# D_Output.net
KiCad netlist of a schematic drawn in Altium Designer
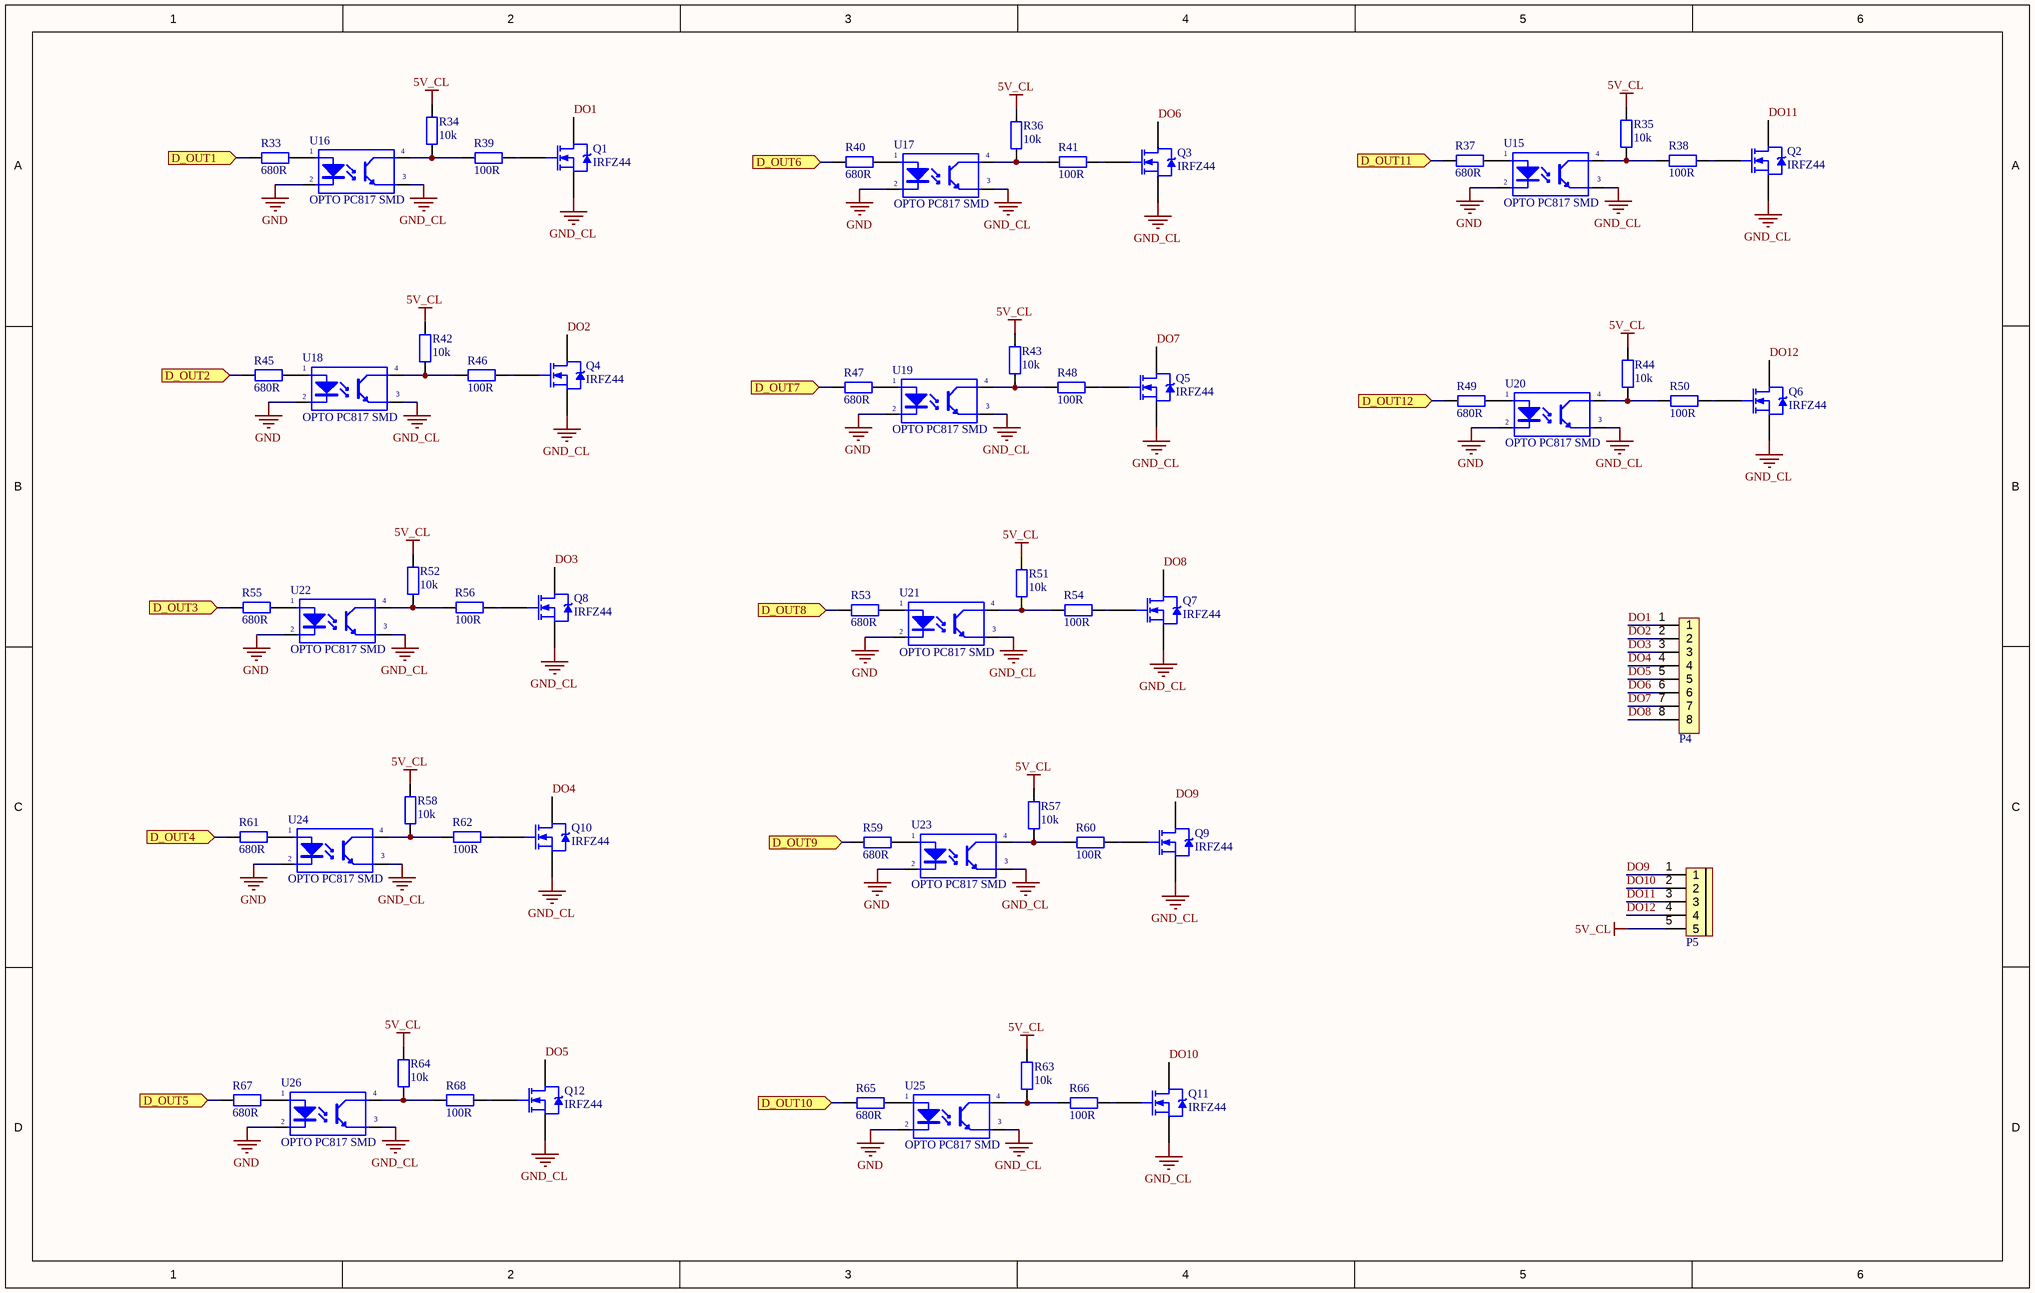
[diagram p0: D_Output.SchDoc]

(export (version "E")
  (design (tool "Eeschema 10.0.6"))
  (components
    (comp (ref "P4")
      (value "CON 8 EDG5.08")
      (footprint "CON 8 8EDG5.08")
      (description "Cắm")
      (libsource (lib "Altium_Lib_by_KhueNguyenCreator") (part "CON 8 EDG5.08"))
    )
    (comp (ref "P5")
      (value "CON 5 EDG5.08")
      (footprint "CON 5 5EDG5.08")
      (description "Cắm")
      (libsource (lib "Altium_Lib_by_KhueNguyenCreator") (part "CON 5 EDG5.08"))
    )
    (comp (ref "Q1")
      (value "IRFZ44")
      (footprint "TO220")
      (description "N-Channel Power MOSFET")
      (libsource (lib "Altium_Lib_by_KhueNguyenCreator") (part "IRFZ44 DIP"))
    )
    (comp (ref "Q2")
      (value "IRFZ44")
      (footprint "TO220")
      (description "N-Channel Power MOSFET")
      (libsource (lib "Altium_Lib_by_KhueNguyenCreator") (part "IRFZ44 DIP"))
    )
    (comp (ref "Q3")
      (value "IRFZ44")
      (footprint "TO220")
      (description "N-Channel Power MOSFET")
      (libsource (lib "Altium_Lib_by_KhueNguyenCreator") (part "IRFZ44 DIP"))
    )
    (comp (ref "Q4")
      (value "IRFZ44")
      (footprint "TO220")
      (description "N-Channel Power MOSFET")
      (libsource (lib "Altium_Lib_by_KhueNguyenCreator") (part "IRFZ44 DIP"))
    )
    (comp (ref "Q5")
      (value "IRFZ44")
      (footprint "TO220")
      (description "N-Channel Power MOSFET")
      (libsource (lib "Altium_Lib_by_KhueNguyenCreator") (part "IRFZ44 DIP"))
    )
    (comp (ref "Q6")
      (value "IRFZ44")
      (footprint "TO220")
      (description "N-Channel Power MOSFET")
      (libsource (lib "Altium_Lib_by_KhueNguyenCreator") (part "IRFZ44 DIP"))
    )
    (comp (ref "Q7")
      (value "IRFZ44")
      (footprint "TO220")
      (description "N-Channel Power MOSFET")
      (libsource (lib "Altium_Lib_by_KhueNguyenCreator") (part "IRFZ44 DIP"))
    )
    (comp (ref "Q8")
      (value "IRFZ44")
      (footprint "TO220")
      (description "N-Channel Power MOSFET")
      (libsource (lib "Altium_Lib_by_KhueNguyenCreator") (part "IRFZ44 DIP"))
    )
    (comp (ref "Q9")
      (value "IRFZ44")
      (footprint "TO220")
      (description "N-Channel Power MOSFET")
      (libsource (lib "Altium_Lib_by_KhueNguyenCreator") (part "IRFZ44 DIP"))
    )
    (comp (ref "Q10")
      (value "IRFZ44")
      (footprint "TO220")
      (description "N-Channel Power MOSFET")
      (libsource (lib "Altium_Lib_by_KhueNguyenCreator") (part "IRFZ44 DIP"))
    )
    (comp (ref "Q11")
      (value "IRFZ44")
      (footprint "TO220")
      (description "N-Channel Power MOSFET")
      (libsource (lib "Altium_Lib_by_KhueNguyenCreator") (part "IRFZ44 DIP"))
    )
    (comp (ref "Q12")
      (value "IRFZ44")
      (footprint "TO220")
      (description "N-Channel Power MOSFET")
      (libsource (lib "Altium_Lib_by_KhueNguyenCreator") (part "IRFZ44 DIP"))
    )
    (comp (ref "R33")
      (value "680R")
      (footprint "tro smd 0805")
      (description "Dán")
      (libsource (lib "Altium_Lib_by_KhueNguyenCreator") (part "Tro 0805 1% 680R"))
    )
    (comp (ref "R34")
      (value "10k")
      (footprint "tro smd 0805")
      (description "Dán")
      (libsource (lib "Altium_Lib_by_KhueNguyenCreator") (part "Tro 0805 1% 10k"))
    )
    (comp (ref "R35")
      (value "10k")
      (footprint "tro smd 0805")
      (description "Dán")
      (libsource (lib "Altium_Lib_by_KhueNguyenCreator") (part "Tro 0805 1% 10k"))
    )
    (comp (ref "R36")
      (value "10k")
      (footprint "tro smd 0805")
      (description "Dán")
      (libsource (lib "Altium_Lib_by_KhueNguyenCreator") (part "Tro 0805 1% 10k"))
    )
    (comp (ref "R37")
      (value "680R")
      (footprint "tro smd 0805")
      (description "Dán")
      (libsource (lib "Altium_Lib_by_KhueNguyenCreator") (part "Tro 0805 1% 680R"))
    )
    (comp (ref "R38")
      (value "100R")
      (footprint "tro smd 0805")
      (description "Dán")
      (libsource (lib "Altium_Lib_by_KhueNguyenCreator") (part "Tro 0805 5% 100R"))
    )
    (comp (ref "R39")
      (value "100R")
      (footprint "tro smd 0805")
      (description "Dán")
      (libsource (lib "Altium_Lib_by_KhueNguyenCreator") (part "Tro 0805 5% 100R"))
    )
    (comp (ref "R40")
      (value "680R")
      (footprint "tro smd 0805")
      (description "Dán")
      (libsource (lib "Altium_Lib_by_KhueNguyenCreator") (part "Tro 0805 1% 680R"))
    )
    (comp (ref "R41")
      (value "100R")
      (footprint "tro smd 0805")
      (description "Dán")
      (libsource (lib "Altium_Lib_by_KhueNguyenCreator") (part "Tro 0805 5% 100R"))
    )
    (comp (ref "R42")
      (value "10k")
      (footprint "tro smd 0805")
      (description "Dán")
      (libsource (lib "Altium_Lib_by_KhueNguyenCreator") (part "Tro 0805 1% 10k"))
    )
    (comp (ref "R43")
      (value "10k")
      (footprint "tro smd 0805")
      (description "Dán")
      (libsource (lib "Altium_Lib_by_KhueNguyenCreator") (part "Tro 0805 1% 10k"))
    )
    (comp (ref "R44")
      (value "10k")
      (footprint "tro smd 0805")
      (description "Dán")
      (libsource (lib "Altium_Lib_by_KhueNguyenCreator") (part "Tro 0805 1% 10k"))
    )
    (comp (ref "R45")
      (value "680R")
      (footprint "tro smd 0805")
      (description "Dán")
      (libsource (lib "Altium_Lib_by_KhueNguyenCreator") (part "Tro 0805 1% 680R"))
    )
    (comp (ref "R46")
      (value "100R")
      (footprint "tro smd 0805")
      (description "Dán")
      (libsource (lib "Altium_Lib_by_KhueNguyenCreator") (part "Tro 0805 5% 100R"))
    )
    (comp (ref "R47")
      (value "680R")
      (footprint "tro smd 0805")
      (description "Dán")
      (libsource (lib "Altium_Lib_by_KhueNguyenCreator") (part "Tro 0805 1% 680R"))
    )
    (comp (ref "R48")
      (value "100R")
      (footprint "tro smd 0805")
      (description "Dán")
      (libsource (lib "Altium_Lib_by_KhueNguyenCreator") (part "Tro 0805 5% 100R"))
    )
    (comp (ref "R49")
      (value "680R")
      (footprint "tro smd 0805")
      (description "Dán")
      (libsource (lib "Altium_Lib_by_KhueNguyenCreator") (part "Tro 0805 1% 680R"))
    )
    (comp (ref "R50")
      (value "100R")
      (footprint "tro smd 0805")
      (description "Dán")
      (libsource (lib "Altium_Lib_by_KhueNguyenCreator") (part "Tro 0805 5% 100R"))
    )
    (comp (ref "R51")
      (value "10k")
      (footprint "tro smd 0805")
      (description "Dán")
      (libsource (lib "Altium_Lib_by_KhueNguyenCreator") (part "Tro 0805 1% 10k"))
    )
    (comp (ref "R52")
      (value "10k")
      (footprint "tro smd 0805")
      (description "Dán")
      (libsource (lib "Altium_Lib_by_KhueNguyenCreator") (part "Tro 0805 1% 10k"))
    )
    (comp (ref "R53")
      (value "680R")
      (footprint "tro smd 0805")
      (description "Dán")
      (libsource (lib "Altium_Lib_by_KhueNguyenCreator") (part "Tro 0805 1% 680R"))
    )
    (comp (ref "R54")
      (value "100R")
      (footprint "tro smd 0805")
      (description "Dán")
      (libsource (lib "Altium_Lib_by_KhueNguyenCreator") (part "Tro 0805 5% 100R"))
    )
    (comp (ref "R55")
      (value "680R")
      (footprint "tro smd 0805")
      (description "Dán")
      (libsource (lib "Altium_Lib_by_KhueNguyenCreator") (part "Tro 0805 1% 680R"))
    )
    (comp (ref "R56")
      (value "100R")
      (footprint "tro smd 0805")
      (description "Dán")
      (libsource (lib "Altium_Lib_by_KhueNguyenCreator") (part "Tro 0805 5% 100R"))
    )
    (comp (ref "R57")
      (value "10k")
      (footprint "tro smd 0805")
      (description "Dán")
      (libsource (lib "Altium_Lib_by_KhueNguyenCreator") (part "Tro 0805 1% 10k"))
    )
    (comp (ref "R58")
      (value "10k")
      (footprint "tro smd 0805")
      (description "Dán")
      (libsource (lib "Altium_Lib_by_KhueNguyenCreator") (part "Tro 0805 1% 10k"))
    )
    (comp (ref "R59")
      (value "680R")
      (footprint "tro smd 0805")
      (description "Dán")
      (libsource (lib "Altium_Lib_by_KhueNguyenCreator") (part "Tro 0805 1% 680R"))
    )
    (comp (ref "R60")
      (value "100R")
      (footprint "tro smd 0805")
      (description "Dán")
      (libsource (lib "Altium_Lib_by_KhueNguyenCreator") (part "Tro 0805 5% 100R"))
    )
    (comp (ref "R61")
      (value "680R")
      (footprint "tro smd 0805")
      (description "Dán")
      (libsource (lib "Altium_Lib_by_KhueNguyenCreator") (part "Tro 0805 1% 680R"))
    )
    (comp (ref "R62")
      (value "100R")
      (footprint "tro smd 0805")
      (description "Dán")
      (libsource (lib "Altium_Lib_by_KhueNguyenCreator") (part "Tro 0805 5% 100R"))
    )
    (comp (ref "R63")
      (value "10k")
      (footprint "tro smd 0805")
      (description "Dán")
      (libsource (lib "Altium_Lib_by_KhueNguyenCreator") (part "Tro 0805 1% 10k"))
    )
    (comp (ref "R64")
      (value "10k")
      (footprint "tro smd 0805")
      (description "Dán")
      (libsource (lib "Altium_Lib_by_KhueNguyenCreator") (part "Tro 0805 1% 10k"))
    )
    (comp (ref "R65")
      (value "680R")
      (footprint "tro smd 0805")
      (description "Dán")
      (libsource (lib "Altium_Lib_by_KhueNguyenCreator") (part "Tro 0805 1% 680R"))
    )
    (comp (ref "R66")
      (value "100R")
      (footprint "tro smd 0805")
      (description "Dán")
      (libsource (lib "Altium_Lib_by_KhueNguyenCreator") (part "Tro 0805 5% 100R"))
    )
    (comp (ref "R67")
      (value "680R")
      (footprint "tro smd 0805")
      (description "Dán")
      (libsource (lib "Altium_Lib_by_KhueNguyenCreator") (part "Tro 0805 1% 680R"))
    )
    (comp (ref "R68")
      (value "100R")
      (footprint "tro smd 0805")
      (description "Dán")
      (libsource (lib "Altium_Lib_by_KhueNguyenCreator") (part "Tro 0805 5% 100R"))
    )
    (comp (ref "U15")
      (value "OPTO PC817 SMD")
      (footprint "SOP4")
      (description "Single Opto")
      (libsource (lib "Altium_Lib_by_KhueNguyenCreator") (part "OPTO PC817 SMD"))
    )
    (comp (ref "U16")
      (value "OPTO PC817 SMD")
      (footprint "SOP4")
      (description "Single Opto")
      (libsource (lib "Altium_Lib_by_KhueNguyenCreator") (part "OPTO PC817 SMD"))
    )
    (comp (ref "U17")
      (value "OPTO PC817 SMD")
      (footprint "SOP4")
      (description "Single Opto")
      (libsource (lib "Altium_Lib_by_KhueNguyenCreator") (part "OPTO PC817 SMD"))
    )
    (comp (ref "U18")
      (value "OPTO PC817 SMD")
      (footprint "SOP4")
      (description "Single Opto")
      (libsource (lib "Altium_Lib_by_KhueNguyenCreator") (part "OPTO PC817 SMD"))
    )
    (comp (ref "U19")
      (value "OPTO PC817 SMD")
      (footprint "SOP4")
      (description "Single Opto")
      (libsource (lib "Altium_Lib_by_KhueNguyenCreator") (part "OPTO PC817 SMD"))
    )
    (comp (ref "U20")
      (value "OPTO PC817 SMD")
      (footprint "SOP4")
      (description "Single Opto")
      (libsource (lib "Altium_Lib_by_KhueNguyenCreator") (part "OPTO PC817 SMD"))
    )
    (comp (ref "U21")
      (value "OPTO PC817 SMD")
      (footprint "SOP4")
      (description "Single Opto")
      (libsource (lib "Altium_Lib_by_KhueNguyenCreator") (part "OPTO PC817 SMD"))
    )
    (comp (ref "U22")
      (value "OPTO PC817 SMD")
      (footprint "SOP4")
      (description "Single Opto")
      (libsource (lib "Altium_Lib_by_KhueNguyenCreator") (part "OPTO PC817 SMD"))
    )
    (comp (ref "U23")
      (value "OPTO PC817 SMD")
      (footprint "SOP4")
      (description "Single Opto")
      (libsource (lib "Altium_Lib_by_KhueNguyenCreator") (part "OPTO PC817 SMD"))
    )
    (comp (ref "U24")
      (value "OPTO PC817 SMD")
      (footprint "SOP4")
      (description "Single Opto")
      (libsource (lib "Altium_Lib_by_KhueNguyenCreator") (part "OPTO PC817 SMD"))
    )
    (comp (ref "U25")
      (value "OPTO PC817 SMD")
      (footprint "SOP4")
      (description "Single Opto")
      (libsource (lib "Altium_Lib_by_KhueNguyenCreator") (part "OPTO PC817 SMD"))
    )
    (comp (ref "U26")
      (value "OPTO PC817 SMD")
      (footprint "SOP4")
      (description "Single Opto")
      (libsource (lib "Altium_Lib_by_KhueNguyenCreator") (part "OPTO PC817 SMD"))
    )
  )
  (nets
    (net (code "1") (name "/DO1") (class "Default")
      (node (ref "P4") (pin "1") (pinfunction "1_1") (pintype "passive"))
      (node (ref "Q1") (pin "2") (pinfunction "D_2") (pintype "passive"))
    )
    (net (code "2") (name "/DO2") (class "Default")
      (node (ref "P4") (pin "2") (pinfunction "2_2") (pintype "passive"))
      (node (ref "Q4") (pin "2") (pinfunction "D_2") (pintype "passive"))
    )
    (net (code "3") (name "/DO3") (class "Default")
      (node (ref "P4") (pin "3") (pinfunction "3_3") (pintype "passive"))
      (node (ref "Q8") (pin "2") (pinfunction "D_2") (pintype "passive"))
    )
    (net (code "4") (name "/DO4") (class "Default")
      (node (ref "P4") (pin "4") (pinfunction "4_4") (pintype "passive"))
      (node (ref "Q10") (pin "2") (pinfunction "D_2") (pintype "passive"))
    )
    (net (code "5") (name "/DO5") (class "Default")
      (node (ref "P4") (pin "5") (pinfunction "5_5") (pintype "passive"))
      (node (ref "Q12") (pin "2") (pinfunction "D_2") (pintype "passive"))
    )
    (net (code "6") (name "/DO6") (class "Default")
      (node (ref "P4") (pin "6") (pinfunction "6_6") (pintype "passive"))
      (node (ref "Q3") (pin "2") (pinfunction "D_2") (pintype "passive"))
    )
    (net (code "7") (name "/DO7") (class "Default")
      (node (ref "P4") (pin "7") (pinfunction "7_7") (pintype "passive"))
      (node (ref "Q5") (pin "2") (pinfunction "D_2") (pintype "passive"))
    )
    (net (code "8") (name "/DO8") (class "Default")
      (node (ref "P4") (pin "8") (pinfunction "8_8") (pintype "passive"))
      (node (ref "Q7") (pin "2") (pinfunction "D_2") (pintype "passive"))
    )
    (net (code "9") (name "/DO9") (class "Default")
      (node (ref "P5") (pin "1") (pinfunction "1_1") (pintype "passive"))
      (node (ref "Q9") (pin "2") (pinfunction "D_2") (pintype "passive"))
    )
    (net (code "10") (name "/DO10") (class "Default")
      (node (ref "P5") (pin "2") (pinfunction "2_2") (pintype "passive"))
      (node (ref "Q11") (pin "2") (pinfunction "D_2") (pintype "passive"))
    )
    (net (code "11") (name "/DO11") (class "Default")
      (node (ref "P5") (pin "3") (pinfunction "3_3") (pintype "passive"))
      (node (ref "Q2") (pin "2") (pinfunction "D_2") (pintype "passive"))
    )
    (net (code "12") (name "/DO12") (class "Default")
      (node (ref "P5") (pin "4") (pinfunction "4_4") (pintype "passive"))
      (node (ref "Q6") (pin "2") (pinfunction "D_2") (pintype "passive"))
    )
    (net (code "13") (name "/D_OUT1") (class "Default")
      (node (ref "R33") (pin "1") (pinfunction "1_1") (pintype "passive"))
    )
    (net (code "14") (name "/D_OUT2") (class "Default")
      (node (ref "R45") (pin "1") (pinfunction "1_1") (pintype "passive"))
    )
    (net (code "15") (name "/D_OUT3") (class "Default")
      (node (ref "R55") (pin "1") (pinfunction "1_1") (pintype "passive"))
    )
    (net (code "16") (name "/D_OUT4") (class "Default")
      (node (ref "R61") (pin "1") (pinfunction "1_1") (pintype "passive"))
    )
    (net (code "17") (name "/D_OUT5") (class "Default")
      (node (ref "R67") (pin "1") (pinfunction "1_1") (pintype "passive"))
    )
    (net (code "18") (name "/D_OUT6") (class "Default")
      (node (ref "R40") (pin "1") (pinfunction "1_1") (pintype "passive"))
    )
    (net (code "19") (name "/D_OUT7") (class "Default")
      (node (ref "R47") (pin "1") (pinfunction "1_1") (pintype "passive"))
    )
    (net (code "20") (name "/D_OUT8") (class "Default")
      (node (ref "R53") (pin "1") (pinfunction "1_1") (pintype "passive"))
    )
    (net (code "21") (name "/D_OUT9") (class "Default")
      (node (ref "R59") (pin "1") (pinfunction "1_1") (pintype "passive"))
    )
    (net (code "22") (name "/D_OUT10") (class "Default")
      (node (ref "R65") (pin "1") (pinfunction "1_1") (pintype "passive"))
    )
    (net (code "23") (name "/D_OUT11") (class "Default")
      (node (ref "R37") (pin "1") (pinfunction "1_1") (pintype "passive"))
    )
    (net (code "24") (name "/D_OUT12") (class "Default")
      (node (ref "R49") (pin "1") (pinfunction "1_1") (pintype "passive"))
    )
    (net (code "25") (name "5V_CL") (class "Default")
      (node (ref "P5") (pin "5") (pinfunction "5_5") (pintype "passive"))
      (node (ref "R34") (pin "1") (pinfunction "1_1") (pintype "passive"))
      (node (ref "R35") (pin "1") (pinfunction "1_1") (pintype "passive"))
      (node (ref "R36") (pin "1") (pinfunction "1_1") (pintype "passive"))
      (node (ref "R42") (pin "1") (pinfunction "1_1") (pintype "passive"))
      (node (ref "R43") (pin "1") (pinfunction "1_1") (pintype "passive"))
      (node (ref "R44") (pin "1") (pinfunction "1_1") (pintype "passive"))
      (node (ref "R51") (pin "1") (pinfunction "1_1") (pintype "passive"))
      (node (ref "R52") (pin "1") (pinfunction "1_1") (pintype "passive"))
      (node (ref "R57") (pin "1") (pinfunction "1_1") (pintype "passive"))
      (node (ref "R58") (pin "1") (pinfunction "1_1") (pintype "passive"))
      (node (ref "R63") (pin "1") (pinfunction "1_1") (pintype "passive"))
      (node (ref "R64") (pin "1") (pinfunction "1_1") (pintype "passive"))
    )
    (net (code "26") (name "GND") (class "Default")
      (node (ref "U15") (pin "2") (pinfunction "K_2") (pintype "passive"))
      (node (ref "U16") (pin "2") (pinfunction "K_2") (pintype "passive"))
      (node (ref "U17") (pin "2") (pinfunction "K_2") (pintype "passive"))
      (node (ref "U18") (pin "2") (pinfunction "K_2") (pintype "passive"))
      (node (ref "U19") (pin "2") (pinfunction "K_2") (pintype "passive"))
      (node (ref "U20") (pin "2") (pinfunction "K_2") (pintype "passive"))
      (node (ref "U21") (pin "2") (pinfunction "K_2") (pintype "passive"))
      (node (ref "U22") (pin "2") (pinfunction "K_2") (pintype "passive"))
      (node (ref "U23") (pin "2") (pinfunction "K_2") (pintype "passive"))
      (node (ref "U24") (pin "2") (pinfunction "K_2") (pintype "passive"))
      (node (ref "U25") (pin "2") (pinfunction "K_2") (pintype "passive"))
      (node (ref "U26") (pin "2") (pinfunction "K_2") (pintype "passive"))
    )
    (net (code "27") (name "GND_CL") (class "Default")
      (node (ref "Q1") (pin "3") (pinfunction "S_3") (pintype "passive"))
      (node (ref "Q10") (pin "3") (pinfunction "S_3") (pintype "passive"))
      (node (ref "Q11") (pin "3") (pinfunction "S_3") (pintype "passive"))
      (node (ref "Q12") (pin "3") (pinfunction "S_3") (pintype "passive"))
      (node (ref "Q2") (pin "3") (pinfunction "S_3") (pintype "passive"))
      (node (ref "Q3") (pin "3") (pinfunction "S_3") (pintype "passive"))
      (node (ref "Q4") (pin "3") (pinfunction "S_3") (pintype "passive"))
      (node (ref "Q5") (pin "3") (pinfunction "S_3") (pintype "passive"))
      (node (ref "Q6") (pin "3") (pinfunction "S_3") (pintype "passive"))
      (node (ref "Q7") (pin "3") (pinfunction "S_3") (pintype "passive"))
      (node (ref "Q8") (pin "3") (pinfunction "S_3") (pintype "passive"))
      (node (ref "Q9") (pin "3") (pinfunction "S_3") (pintype "passive"))
      (node (ref "U15") (pin "3") (pinfunction "E_3") (pintype "passive"))
      (node (ref "U16") (pin "3") (pinfunction "E_3") (pintype "passive"))
      (node (ref "U17") (pin "3") (pinfunction "E_3") (pintype "passive"))
      (node (ref "U18") (pin "3") (pinfunction "E_3") (pintype "passive"))
      (node (ref "U19") (pin "3") (pinfunction "E_3") (pintype "passive"))
      (node (ref "U20") (pin "3") (pinfunction "E_3") (pintype "passive"))
      (node (ref "U21") (pin "3") (pinfunction "E_3") (pintype "passive"))
      (node (ref "U22") (pin "3") (pinfunction "E_3") (pintype "passive"))
      (node (ref "U23") (pin "3") (pinfunction "E_3") (pintype "passive"))
      (node (ref "U24") (pin "3") (pinfunction "E_3") (pintype "passive"))
      (node (ref "U25") (pin "3") (pinfunction "E_3") (pintype "passive"))
      (node (ref "U26") (pin "3") (pinfunction "E_3") (pintype "passive"))
    )
    (net (code "28") (name "Net-(Q1-G)") (class "Default")
      (node (ref "Q1") (pin "1") (pinfunction "G_1") (pintype "passive"))
      (node (ref "R39") (pin "2") (pinfunction "2_2") (pintype "passive"))
    )
    (net (code "29") (name "Net-(Q2-G)") (class "Default")
      (node (ref "Q2") (pin "1") (pinfunction "G_1") (pintype "passive"))
      (node (ref "R38") (pin "2") (pinfunction "2_2") (pintype "passive"))
    )
    (net (code "30") (name "Net-(Q3-G)") (class "Default")
      (node (ref "Q3") (pin "1") (pinfunction "G_1") (pintype "passive"))
      (node (ref "R41") (pin "2") (pinfunction "2_2") (pintype "passive"))
    )
    (net (code "31") (name "Net-(Q4-G)") (class "Default")
      (node (ref "Q4") (pin "1") (pinfunction "G_1") (pintype "passive"))
      (node (ref "R46") (pin "2") (pinfunction "2_2") (pintype "passive"))
    )
    (net (code "32") (name "Net-(Q5-G)") (class "Default")
      (node (ref "Q5") (pin "1") (pinfunction "G_1") (pintype "passive"))
      (node (ref "R48") (pin "2") (pinfunction "2_2") (pintype "passive"))
    )
    (net (code "33") (name "Net-(Q6-G)") (class "Default")
      (node (ref "Q6") (pin "1") (pinfunction "G_1") (pintype "passive"))
      (node (ref "R50") (pin "2") (pinfunction "2_2") (pintype "passive"))
    )
    (net (code "34") (name "Net-(Q7-G)") (class "Default")
      (node (ref "Q7") (pin "1") (pinfunction "G_1") (pintype "passive"))
      (node (ref "R54") (pin "2") (pinfunction "2_2") (pintype "passive"))
    )
    (net (code "35") (name "Net-(Q8-G)") (class "Default")
      (node (ref "Q8") (pin "1") (pinfunction "G_1") (pintype "passive"))
      (node (ref "R56") (pin "2") (pinfunction "2_2") (pintype "passive"))
    )
    (net (code "36") (name "Net-(Q9-G)") (class "Default")
      (node (ref "Q9") (pin "1") (pinfunction "G_1") (pintype "passive"))
      (node (ref "R60") (pin "2") (pinfunction "2_2") (pintype "passive"))
    )
    (net (code "37") (name "Net-(Q10-G)") (class "Default")
      (node (ref "Q10") (pin "1") (pinfunction "G_1") (pintype "passive"))
      (node (ref "R62") (pin "2") (pinfunction "2_2") (pintype "passive"))
    )
    (net (code "38") (name "Net-(Q11-G)") (class "Default")
      (node (ref "Q11") (pin "1") (pinfunction "G_1") (pintype "passive"))
      (node (ref "R66") (pin "2") (pinfunction "2_2") (pintype "passive"))
    )
    (net (code "39") (name "Net-(Q12-G)") (class "Default")
      (node (ref "Q12") (pin "1") (pinfunction "G_1") (pintype "passive"))
      (node (ref "R68") (pin "2") (pinfunction "2_2") (pintype "passive"))
    )
    (net (code "40") (name "Net-(U15-A)") (class "Default")
      (node (ref "R37") (pin "2") (pinfunction "2_2") (pintype "passive"))
      (node (ref "U15") (pin "1") (pinfunction "A_1") (pintype "passive"))
    )
    (net (code "41") (name "Net-(U15-C)") (class "Default")
      (node (ref "R35") (pin "2") (pinfunction "2_2") (pintype "passive"))
      (node (ref "R38") (pin "1") (pinfunction "1_1") (pintype "passive"))
      (node (ref "U15") (pin "4") (pinfunction "C_4") (pintype "passive"))
    )
    (net (code "42") (name "Net-(U16-A)") (class "Default")
      (node (ref "R33") (pin "2") (pinfunction "2_2") (pintype "passive"))
      (node (ref "U16") (pin "1") (pinfunction "A_1") (pintype "passive"))
    )
    (net (code "43") (name "Net-(U16-C)") (class "Default")
      (node (ref "R34") (pin "2") (pinfunction "2_2") (pintype "passive"))
      (node (ref "R39") (pin "1") (pinfunction "1_1") (pintype "passive"))
      (node (ref "U16") (pin "4") (pinfunction "C_4") (pintype "passive"))
    )
    (net (code "44") (name "Net-(U17-A)") (class "Default")
      (node (ref "R40") (pin "2") (pinfunction "2_2") (pintype "passive"))
      (node (ref "U17") (pin "1") (pinfunction "A_1") (pintype "passive"))
    )
    (net (code "45") (name "Net-(U17-C)") (class "Default")
      (node (ref "R36") (pin "2") (pinfunction "2_2") (pintype "passive"))
      (node (ref "R41") (pin "1") (pinfunction "1_1") (pintype "passive"))
      (node (ref "U17") (pin "4") (pinfunction "C_4") (pintype "passive"))
    )
    (net (code "46") (name "Net-(U18-A)") (class "Default")
      (node (ref "R45") (pin "2") (pinfunction "2_2") (pintype "passive"))
      (node (ref "U18") (pin "1") (pinfunction "A_1") (pintype "passive"))
    )
    (net (code "47") (name "Net-(U18-C)") (class "Default")
      (node (ref "R42") (pin "2") (pinfunction "2_2") (pintype "passive"))
      (node (ref "R46") (pin "1") (pinfunction "1_1") (pintype "passive"))
      (node (ref "U18") (pin "4") (pinfunction "C_4") (pintype "passive"))
    )
    (net (code "48") (name "Net-(U19-A)") (class "Default")
      (node (ref "R47") (pin "2") (pinfunction "2_2") (pintype "passive"))
      (node (ref "U19") (pin "1") (pinfunction "A_1") (pintype "passive"))
    )
    (net (code "49") (name "Net-(U19-C)") (class "Default")
      (node (ref "R43") (pin "2") (pinfunction "2_2") (pintype "passive"))
      (node (ref "R48") (pin "1") (pinfunction "1_1") (pintype "passive"))
      (node (ref "U19") (pin "4") (pinfunction "C_4") (pintype "passive"))
    )
    (net (code "50") (name "Net-(U20-A)") (class "Default")
      (node (ref "R49") (pin "2") (pinfunction "2_2") (pintype "passive"))
      (node (ref "U20") (pin "1") (pinfunction "A_1") (pintype "passive"))
    )
    (net (code "51") (name "Net-(U20-C)") (class "Default")
      (node (ref "R44") (pin "2") (pinfunction "2_2") (pintype "passive"))
      (node (ref "R50") (pin "1") (pinfunction "1_1") (pintype "passive"))
      (node (ref "U20") (pin "4") (pinfunction "C_4") (pintype "passive"))
    )
    (net (code "52") (name "Net-(U21-A)") (class "Default")
      (node (ref "R53") (pin "2") (pinfunction "2_2") (pintype "passive"))
      (node (ref "U21") (pin "1") (pinfunction "A_1") (pintype "passive"))
    )
    (net (code "53") (name "Net-(U21-C)") (class "Default")
      (node (ref "R51") (pin "2") (pinfunction "2_2") (pintype "passive"))
      (node (ref "R54") (pin "1") (pinfunction "1_1") (pintype "passive"))
      (node (ref "U21") (pin "4") (pinfunction "C_4") (pintype "passive"))
    )
    (net (code "54") (name "Net-(U22-A)") (class "Default")
      (node (ref "R55") (pin "2") (pinfunction "2_2") (pintype "passive"))
      (node (ref "U22") (pin "1") (pinfunction "A_1") (pintype "passive"))
    )
    (net (code "55") (name "Net-(U22-C)") (class "Default")
      (node (ref "R52") (pin "2") (pinfunction "2_2") (pintype "passive"))
      (node (ref "R56") (pin "1") (pinfunction "1_1") (pintype "passive"))
      (node (ref "U22") (pin "4") (pinfunction "C_4") (pintype "passive"))
    )
    (net (code "56") (name "Net-(U23-A)") (class "Default")
      (node (ref "R59") (pin "2") (pinfunction "2_2") (pintype "passive"))
      (node (ref "U23") (pin "1") (pinfunction "A_1") (pintype "passive"))
    )
    (net (code "57") (name "Net-(U23-C)") (class "Default")
      (node (ref "R57") (pin "2") (pinfunction "2_2") (pintype "passive"))
      (node (ref "R60") (pin "1") (pinfunction "1_1") (pintype "passive"))
      (node (ref "U23") (pin "4") (pinfunction "C_4") (pintype "passive"))
    )
    (net (code "58") (name "Net-(U24-A)") (class "Default")
      (node (ref "R61") (pin "2") (pinfunction "2_2") (pintype "passive"))
      (node (ref "U24") (pin "1") (pinfunction "A_1") (pintype "passive"))
    )
    (net (code "59") (name "Net-(U24-C)") (class "Default")
      (node (ref "R58") (pin "2") (pinfunction "2_2") (pintype "passive"))
      (node (ref "R62") (pin "1") (pinfunction "1_1") (pintype "passive"))
      (node (ref "U24") (pin "4") (pinfunction "C_4") (pintype "passive"))
    )
    (net (code "60") (name "Net-(U25-A)") (class "Default")
      (node (ref "R65") (pin "2") (pinfunction "2_2") (pintype "passive"))
      (node (ref "U25") (pin "1") (pinfunction "A_1") (pintype "passive"))
    )
    (net (code "61") (name "Net-(U25-C)") (class "Default")
      (node (ref "R63") (pin "2") (pinfunction "2_2") (pintype "passive"))
      (node (ref "R66") (pin "1") (pinfunction "1_1") (pintype "passive"))
      (node (ref "U25") (pin "4") (pinfunction "C_4") (pintype "passive"))
    )
    (net (code "62") (name "Net-(U26-A)") (class "Default")
      (node (ref "R67") (pin "2") (pinfunction "2_2") (pintype "passive"))
      (node (ref "U26") (pin "1") (pinfunction "A_1") (pintype "passive"))
    )
    (net (code "63") (name "Net-(U26-C)") (class "Default")
      (node (ref "R64") (pin "2") (pinfunction "2_2") (pintype "passive"))
      (node (ref "R68") (pin "1") (pinfunction "1_1") (pintype "passive"))
      (node (ref "U26") (pin "4") (pinfunction "C_4") (pintype "passive"))
    )
  )
)
